# RCShield-avr-v4.net
KiCad netlist of a schematic drawn in EAGLE
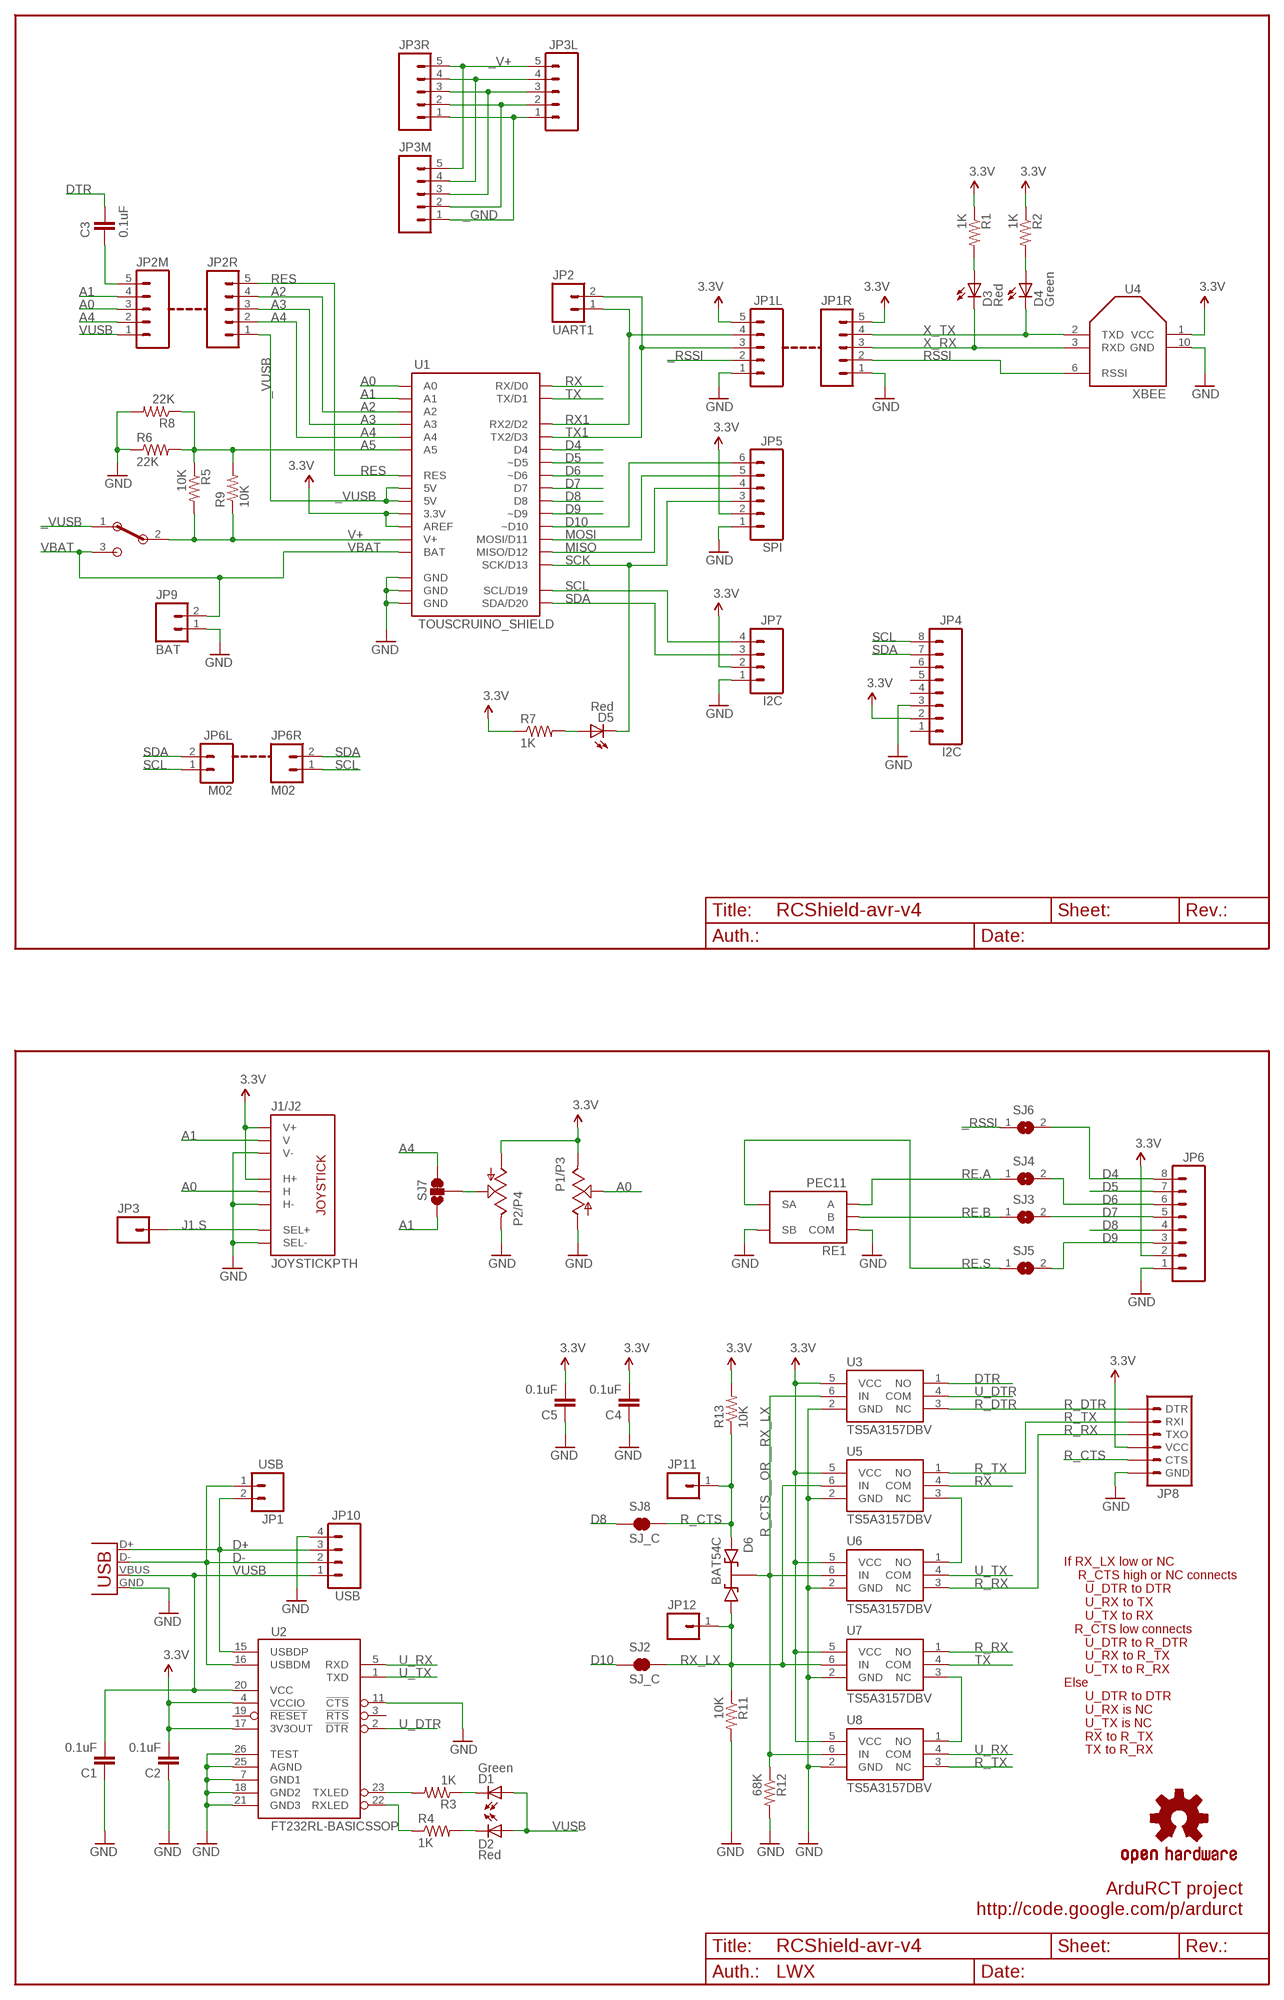
[diagram p0: schematic, sheet 1]

(export (version "E")
  (design (tool "Eeschema 10.0.6"))
  (components
    (comp (ref "C1")
      (value "0.1uF")
      (footprint "eagle-import:0805")
      (libsource (lib "eagle-import") (part "CAP0805"))
    )
    (comp (ref "C2")
      (value "0.1uF")
      (footprint "eagle-import:0805")
      (libsource (lib "eagle-import") (part "CAP0805"))
    )
    (comp (ref "C3")
      (value "0.1uF")
      (footprint "eagle-import:0805")
      (libsource (lib "eagle-import") (part "CAP0805"))
    )
    (comp (ref "C4")
      (value "0.1uF")
      (footprint "eagle-import:0805")
      (libsource (lib "eagle-import") (part "CAP0805"))
    )
    (comp (ref "C5")
      (value "0.1uF")
      (footprint "eagle-import:0805")
      (libsource (lib "eagle-import") (part "CAP0805"))
    )
    (comp (ref "D1")
      (value "Green")
      (footprint "eagle-import:LED")
      (libsource (lib "eagle-import") (part "LED"))
    )
    (comp (ref "D2")
      (value "Red")
      (footprint "eagle-import:LED")
      (libsource (lib "eagle-import") (part "LED"))
    )
    (comp (ref "D3")
      (value "Red")
      (footprint "eagle-import:LED")
      (libsource (lib "eagle-import") (part "LED"))
    )
    (comp (ref "D4")
      (value "Green")
      (footprint "eagle-import:LED")
      (libsource (lib "eagle-import") (part "LED"))
    )
    (comp (ref "D5")
      (value "Red")
      (footprint "eagle-import:LED")
      (libsource (lib "eagle-import") (part "LED"))
    )
    (comp (ref "D6")
      (value "BAT54C")
      (footprint "eagle-import:SOT23-3")
      (libsource (lib "eagle-import") (part "BAT54C"))
    )
    (comp (ref "J1/J2")
      (value "JOYSTICKPTH")
      (footprint "eagle-import:JOYSTICK")
      (libsource (lib "eagle-import") (part "JOYSTICKPTH"))
    )
    (comp (ref "JP1")
      (value "USB")
      (footprint "eagle-import:1X02")
      (libsource (lib "eagle-import") (part "M02"))
    )
    (comp (ref "JP1L")
      (value "M05")
      (footprint "eagle-import:2+3")
      (libsource (lib "eagle-import") (part "M05"))
    )
    (comp (ref "JP1R")
      (value "M05")
      (footprint "eagle-import:2+3")
      (libsource (lib "eagle-import") (part "M05"))
    )
    (comp (ref "JP2")
      (value "UART1")
      (footprint "eagle-import:1X02")
      (libsource (lib "eagle-import") (part "M02"))
    )
    (comp (ref "JP2M")
      (value "M05")
      (footprint "eagle-import:2+3")
      (libsource (lib "eagle-import") (part "M05"))
    )
    (comp (ref "JP2R")
      (value "M05")
      (footprint "eagle-import:2+3")
      (libsource (lib "eagle-import") (part "M05"))
    )
    (comp (ref "JP3")
      (value "M01PTH")
      (footprint "eagle-import:1X01")
      (libsource (lib "eagle-import") (part "M01PTH"))
    )
    (comp (ref "JP3L")
      (value "M05")
      (footprint "eagle-import:2+3")
      (libsource (lib "eagle-import") (part "M05"))
    )
    (comp (ref "JP3M")
      (value "M05")
      (footprint "eagle-import:2+3")
      (libsource (lib "eagle-import") (part "M05"))
    )
    (comp (ref "JP3R")
      (value "M05")
      (footprint "eagle-import:2+3")
      (libsource (lib "eagle-import") (part "M05"))
    )
    (comp (ref "JP4")
      (value "I2C")
      (footprint "eagle-import:1X08")
      (libsource (lib "eagle-import") (part "M08"))
    )
    (comp (ref "JP5")
      (value "SPI")
      (footprint "eagle-import:1X06")
      (libsource (lib "eagle-import") (part "M06SIP"))
    )
    (comp (ref "JP6")
      (value "M08")
      (footprint "eagle-import:1X08")
      (libsource (lib "eagle-import") (part "M08"))
    )
    (comp (ref "JP6L")
      (value "M02")
      (footprint "eagle-import:1X02")
      (libsource (lib "eagle-import") (part "M02"))
    )
    (comp (ref "JP6R")
      (value "M02")
      (footprint "eagle-import:1X02")
      (libsource (lib "eagle-import") (part "M02"))
    )
    (comp (ref "JP7")
      (value "I2C")
      (footprint "eagle-import:1X04")
      (libsource (lib "eagle-import") (part "M04"))
    )
    (comp (ref "JP8")
      (value "ARDUINO_SERIAL_PROGRAM")
      (footprint "eagle-import:1X06_F")
      (libsource (lib "eagle-import") (part "ARDUINO_SERIAL_PROGRAM"))
    )
    (comp (ref "JP9")
      (value "BAT")
      (footprint "eagle-import:1X02")
      (libsource (lib "eagle-import") (part "M02"))
    )
    (comp (ref "JP10")
      (value "USB")
      (footprint "eagle-import:1X04")
      (libsource (lib "eagle-import") (part "M04"))
    )
    (comp (ref "JP11")
      (value "M01SMALL")
      (footprint "eagle-import:1X01_S")
      (libsource (lib "eagle-import") (part "M01SMALL"))
    )
    (comp (ref "JP12")
      (value "M01SMALL")
      (footprint "eagle-import:1X01_S")
      (libsource (lib "eagle-import") (part "M01SMALL"))
    )
    (comp (ref "P1/P3")
      (value "POT")
      (footprint "eagle-import:ALPS_POT")
      (libsource (lib "eagle-import") (part "POT"))
    )
    (comp (ref "P2/P4")
      (value "POT")
      (footprint "eagle-import:ALPS_POT")
      (libsource (lib "eagle-import") (part "POT"))
    )
    (comp (ref "R1")
      (value "1K")
      (footprint "eagle-import:0805")
      (libsource (lib "eagle-import") (part "RESISTOR0805-RES"))
    )
    (comp (ref "R2")
      (value "1K")
      (footprint "eagle-import:0805")
      (libsource (lib "eagle-import") (part "RESISTOR0805-RES"))
    )
    (comp (ref "R3")
      (value "1K")
      (footprint "eagle-import:0805")
      (libsource (lib "eagle-import") (part "RESISTOR0805-RES"))
    )
    (comp (ref "R4")
      (value "1K")
      (footprint "eagle-import:0805")
      (libsource (lib "eagle-import") (part "RESISTOR0805-RES"))
    )
    (comp (ref "R5")
      (value "10K")
      (footprint "eagle-import:0805")
      (libsource (lib "eagle-import") (part "RESISTOR0805-RES"))
    )
    (comp (ref "R6")
      (value "22K")
      (footprint "eagle-import:0805")
      (libsource (lib "eagle-import") (part "RESISTOR0805-RES"))
    )
    (comp (ref "R7")
      (value "1K")
      (footprint "eagle-import:0805")
      (libsource (lib "eagle-import") (part "RESISTOR0805-RES"))
    )
    (comp (ref "R8")
      (value "22K")
      (footprint "eagle-import:0207_7")
      (libsource (lib "eagle-import") (part "R-US_0207/7"))
    )
    (comp (ref "R9")
      (value "10K")
      (footprint "eagle-import:0207_7")
      (libsource (lib "eagle-import") (part "R-US_0207/7"))
    )
    (comp (ref "R11")
      (value "10K")
      (footprint "eagle-import:0805")
      (libsource (lib "eagle-import") (part "RESISTOR0805-RES"))
    )
    (comp (ref "R12")
      (value "68K")
      (footprint "eagle-import:0805")
      (libsource (lib "eagle-import") (part "RESISTOR0805-RES"))
    )
    (comp (ref "R13")
      (value "10K")
      (footprint "eagle-import:0805")
      (libsource (lib "eagle-import") (part "RESISTOR0805-RES"))
    )
    (comp (ref "RE1")
      (value "PEC11")
      (footprint "eagle-import:PEC11")
      (libsource (lib "eagle-import") (part "PEC11"))
    )
    (comp (ref "S4")
      (value "EG1224")
      (footprint "eagle-import:EG1224")
      (libsource (lib "eagle-import") (part "EG1224"))
    )
    (comp (ref "SJ2")
      (value "SJ_C")
      (footprint "eagle-import:SJ_C")
      (libsource (lib "eagle-import") (part "SJ_C"))
    )
    (comp (ref "SJ3") (value "SJ") (footprint "eagle-import:SJ") (libsource (lib "eagle-import") (part "SJ")))
    (comp (ref "SJ4") (value "SJ") (footprint "eagle-import:SJ") (libsource (lib "eagle-import") (part "SJ")))
    (comp (ref "SJ5") (value "SJ") (footprint "eagle-import:SJ") (libsource (lib "eagle-import") (part "SJ")))
    (comp (ref "SJ6") (value "SJ") (footprint "eagle-import:SJ") (libsource (lib "eagle-import") (part "SJ")))
    (comp (ref "SJ7")
      (value "SJ_2WAYS_1-2W")
      (footprint "eagle-import:SJ_2WAYS_1-2")
      (libsource (lib "eagle-import") (part "SJ_2WAYS_1-2W"))
    )
    (comp (ref "SJ8")
      (value "SJ_C")
      (footprint "eagle-import:SJ_C")
      (libsource (lib "eagle-import") (part "SJ_C"))
    )
    (comp (ref "U$1")
      (value "OSHW-LOGOM")
      (footprint "eagle-import:OSHW-LOGO-M")
      (libsource (lib "eagle-import") (part "OSHW-LOGOM"))
    )
    (comp (ref "U1")
      (value "TOUSCRUINO_SHIELD")
      (footprint "eagle-import:TOUSCRUINO_SHIELD_SPLIT")
      (libsource (lib "eagle-import") (part "TOUSCRUINO_SHIELDSPLIT"))
    )
    (comp (ref "U2")
      (value "FT232RL-BASICSSOP")
      (footprint "eagle-import:SSOP28DB")
      (libsource (lib "eagle-import") (part "FT232RL-BASICSSOP"))
    )
    (comp (ref "U3")
      (value "TS5A3157DBV")
      (footprint "eagle-import:SOT23-6")
      (libsource (lib "eagle-import") (part "TS5A3157DBV"))
    )
    (comp (ref "U4")
      (value "XBEE")
      (footprint "eagle-import:XBEE-SMD")
      (libsource (lib "eagle-import") (part "XBEE-RSSI"))
    )
    (comp (ref "U5")
      (value "TS5A3157DBV")
      (footprint "eagle-import:SOT23-6")
      (libsource (lib "eagle-import") (part "TS5A3157DBV"))
    )
    (comp (ref "U6")
      (value "TS5A3157DBV")
      (footprint "eagle-import:SOT23-6")
      (libsource (lib "eagle-import") (part "TS5A3157DBV"))
    )
    (comp (ref "U7")
      (value "TS5A3157DBV")
      (footprint "eagle-import:SOT23-6")
      (libsource (lib "eagle-import") (part "TS5A3157DBV"))
    )
    (comp (ref "U8")
      (value "TS5A3157DBV")
      (footprint "eagle-import:SOT23-6")
      (libsource (lib "eagle-import") (part "TS5A3157DBV"))
    )
    (comp (ref "X1")
      (value "USB")
      (footprint "eagle-import:USB-MICROB")
      (libsource (lib "eagle-import") (part "USB"))
    )
  )
  (nets
    (net (code "1") (name "/A0") (class "Default")
      (node (ref "J1/J2") (pin "H2") (pinfunction "H_H2") (pintype "bidirectional"))
      (node (ref "JP2M") (pin "3") (pinfunction "3_3") (pintype "passive"))
      (node (ref "P1/P3") (pin "P$2") (pinfunction "S_P$2") (pintype "passive"))
      (node (ref "U1") (pin "A0") (pinfunction "A0_A0") (pintype "bidirectional"))
    )
    (net (code "2") (name "/A1") (class "Default")
      (node (ref "J1/J2") (pin "V2") (pinfunction "V_V2") (pintype "bidirectional"))
      (node (ref "JP2M") (pin "4") (pinfunction "4_4") (pintype "passive"))
      (node (ref "SJ7") (pin "3") (pinfunction "3_3") (pintype "passive"))
      (node (ref "U1") (pin "A1") (pinfunction "A1_A1") (pintype "bidirectional"))
    )
    (net (code "3") (name "/A2") (class "Default")
      (node (ref "JP2R") (pin "4") (pinfunction "4_4") (pintype "passive"))
      (node (ref "U1") (pin "A2") (pinfunction "A2_A2") (pintype "bidirectional"))
    )
    (net (code "4") (name "/A3") (class "Default")
      (node (ref "JP2R") (pin "3") (pinfunction "3_3") (pintype "passive"))
      (node (ref "U1") (pin "A3") (pinfunction "A3_A3") (pintype "bidirectional"))
    )
    (net (code "5") (name "/A4") (class "Default")
      (node (ref "JP2M") (pin "2") (pinfunction "2_2") (pintype "passive"))
      (node (ref "JP2R") (pin "2") (pinfunction "2_2") (pintype "passive"))
      (node (ref "SJ7") (pin "1") (pinfunction "1_1") (pintype "passive"))
      (node (ref "U1") (pin "A4") (pinfunction "A4_A4") (pintype "bidirectional"))
    )
    (net (code "6") (name "/A5") (class "Default")
      (node (ref "R5") (pin "1") (pinfunction "1_1") (pintype "passive"))
      (node (ref "R6") (pin "2") (pinfunction "2_2") (pintype "passive"))
      (node (ref "R8") (pin "1") (pinfunction "1_1") (pintype "passive"))
      (node (ref "R9") (pin "2") (pinfunction "2_2") (pintype "passive"))
      (node (ref "U1") (pin "A5") (pinfunction "A5_A5") (pintype "bidirectional"))
    )
    (net (code "7") (name "/D+") (class "Default")
      (node (ref "JP1") (pin "2") (pinfunction "2_2") (pintype "passive"))
      (node (ref "JP10") (pin "3") (pinfunction "3_3") (pintype "passive"))
      (node (ref "U2") (pin "15") (pinfunction "USBDP_15") (pintype "bidirectional"))
      (node (ref "X1") (pin "D+") (pinfunction "D+_D+") (pintype "bidirectional"))
    )
    (net (code "8") (name "/D-") (class "Default")
      (node (ref "JP1") (pin "1") (pinfunction "1_1") (pintype "passive"))
      (node (ref "JP10") (pin "2") (pinfunction "2_2") (pintype "passive"))
      (node (ref "U2") (pin "16") (pinfunction "USBDM_16") (pintype "bidirectional"))
      (node (ref "X1") (pin "D-") (pinfunction "D-_D-") (pintype "bidirectional"))
    )
    (net (code "9") (name "/D4") (class "Default")
      (node (ref "JP6") (pin "8") (pinfunction "8_8") (pintype "passive"))
      (node (ref "SJ6") (pin "2") (pinfunction "2_2") (pintype "passive"))
      (node (ref "U1") (pin "D4") (pinfunction "D4_D4") (pintype "bidirectional"))
    )
    (net (code "10") (name "/D5") (class "Default")
      (node (ref "JP6") (pin "7") (pinfunction "7_7") (pintype "passive"))
      (node (ref "U1") (pin "D5") (pinfunction "~{D5}_D5") (pintype "bidirectional"))
    )
    (net (code "11") (name "/D6") (class "Default")
      (node (ref "JP6") (pin "6") (pinfunction "6_6") (pintype "passive"))
      (node (ref "SJ4") (pin "2") (pinfunction "2_2") (pintype "passive"))
      (node (ref "U1") (pin "D6") (pinfunction "~{D6}_D6") (pintype "bidirectional"))
    )
    (net (code "12") (name "/D7") (class "Default")
      (node (ref "JP6") (pin "5") (pinfunction "5_5") (pintype "passive"))
      (node (ref "SJ3") (pin "2") (pinfunction "2_2") (pintype "passive"))
      (node (ref "U1") (pin "D7") (pinfunction "D7_D7") (pintype "bidirectional"))
    )
    (net (code "13") (name "/D8") (class "Default")
      (node (ref "JP6") (pin "4") (pinfunction "4_4") (pintype "passive"))
      (node (ref "SJ8") (pin "1") (pinfunction "1_1") (pintype "passive"))
      (node (ref "U1") (pin "D8") (pinfunction "D8_D8") (pintype "bidirectional"))
    )
    (net (code "14") (name "/D9") (class "Default")
      (node (ref "JP6") (pin "3") (pinfunction "3_3") (pintype "passive"))
      (node (ref "SJ5") (pin "2") (pinfunction "2_2") (pintype "passive"))
      (node (ref "U1") (pin "D9") (pinfunction "~{D9}_D9") (pintype "bidirectional"))
    )
    (net (code "15") (name "/D10") (class "Default")
      (node (ref "JP5") (pin "6") (pinfunction "6_6") (pintype "passive"))
      (node (ref "SJ2") (pin "1") (pinfunction "1_1") (pintype "passive"))
      (node (ref "U1") (pin "D10") (pinfunction "~{D10}_D10") (pintype "bidirectional"))
    )
    (net (code "16") (name "/DTR") (class "Default")
      (node (ref "C3") (pin "1") (pinfunction "1_1") (pintype "passive"))
      (node (ref "U3") (pin "1") (pinfunction "NO_1") (pintype "bidirectional"))
    )
    (net (code "17") (name "/J1.S") (class "Default")
      (node (ref "J1/J2") (pin "B1A") (pinfunction "SEL+_B1A") (pintype "bidirectional"))
      (node (ref "JP3") (pin "1") (pinfunction "1_1") (pintype "passive"))
    )
    (net (code "18") (name "/MISO") (class "Default")
      (node (ref "JP5") (pin "4") (pinfunction "4_4") (pintype "passive"))
      (node (ref "U1") (pin "D12") (pinfunction "MISO/D12_D12") (pintype "bidirectional"))
    )
    (net (code "19") (name "/MOSI") (class "Default")
      (node (ref "JP5") (pin "5") (pinfunction "5_5") (pintype "passive"))
      (node (ref "U1") (pin "D11") (pinfunction "MOSI/D11_D11") (pintype "bidirectional"))
    )
    (net (code "20") (name "/RE.A") (class "Default")
      (node (ref "RE1") (pin "A") (pinfunction "A_A") (pintype "bidirectional"))
      (node (ref "SJ4") (pin "1") (pinfunction "1_1") (pintype "passive"))
    )
    (net (code "21") (name "/RE.B") (class "Default")
      (node (ref "RE1") (pin "B") (pinfunction "B_B") (pintype "bidirectional"))
      (node (ref "SJ3") (pin "1") (pinfunction "1_1") (pintype "passive"))
    )
    (net (code "22") (name "/RE.S") (class "Default")
      (node (ref "RE1") (pin "S1") (pinfunction "SA_S1") (pintype "bidirectional"))
      (node (ref "SJ5") (pin "1") (pinfunction "1_1") (pintype "passive"))
    )
    (net (code "23") (name "/RES") (class "Default")
      (node (ref "JP2R") (pin "5") (pinfunction "5_5") (pintype "passive"))
      (node (ref "U1") (pin "RES") (pinfunction "RES_RES") (pintype "bidirectional"))
    )
    (net (code "24") (name "/RSSI") (class "Default")
      (node (ref "JP1R") (pin "2") (pinfunction "2_2") (pintype "passive"))
      (node (ref "U4") (pin "6") (pinfunction "RSSI_6") (pintype "bidirectional"))
    )
    (net (code "25") (name "/RX") (class "Default")
      (node (ref "U1") (pin "RX") (pinfunction "RX/D0_RX") (pintype "bidirectional"))
      (node (ref "U5") (pin "4") (pinfunction "COM_4") (pintype "bidirectional"))
    )
    (net (code "26") (name "/RX1") (class "Default")
      (node (ref "JP1L") (pin "4") (pinfunction "4_4") (pintype "passive"))
      (node (ref "JP2") (pin "1") (pinfunction "1_1") (pintype "passive"))
      (node (ref "U1") (pin "D2") (pinfunction "RX2/D2_D2") (pintype "bidirectional"))
    )
    (net (code "27") (name "/RX_LX") (class "Default")
      (node (ref "D6") (pin "1") (pinfunction "A1_1") (pintype "bidirectional"))
      (node (ref "JP12") (pin "1") (pinfunction "1_1") (pintype "passive"))
      (node (ref "R11") (pin "1") (pinfunction "1_1") (pintype "passive"))
      (node (ref "SJ2") (pin "2") (pinfunction "2_2") (pintype "passive"))
      (node (ref "U5") (pin "6") (pinfunction "IN_6") (pintype "bidirectional"))
      (node (ref "U7") (pin "6") (pinfunction "IN_6") (pintype "bidirectional"))
    )
    (net (code "28") (name "/R_CTS") (class "Default")
      (node (ref "D6") (pin "2") (pinfunction "A2_2") (pintype "bidirectional"))
      (node (ref "JP11") (pin "1") (pinfunction "1_1") (pintype "passive"))
      (node (ref "JP8") (pin "5") (pinfunction "CTS_5") (pintype "passive"))
      (node (ref "R13") (pin "1") (pinfunction "1_1") (pintype "passive"))
      (node (ref "SJ8") (pin "2") (pinfunction "2_2") (pintype "passive"))
    )
    (net (code "29") (name "/R_CTS__OR__RX_LX") (class "Default")
      (node (ref "D6") (pin "3") (pinfunction "K_3") (pintype "bidirectional"))
      (node (ref "R12") (pin "1") (pinfunction "1_1") (pintype "passive"))
      (node (ref "U3") (pin "6") (pinfunction "IN_6") (pintype "bidirectional"))
      (node (ref "U6") (pin "6") (pinfunction "IN_6") (pintype "bidirectional"))
      (node (ref "U8") (pin "6") (pinfunction "IN_6") (pintype "bidirectional"))
    )
    (net (code "30") (name "/R_DTR") (class "Default")
      (node (ref "JP8") (pin "1") (pinfunction "DTR_1") (pintype "passive"))
      (node (ref "U3") (pin "3") (pinfunction "NC_3") (pintype "bidirectional"))
    )
    (net (code "31") (name "/R_RX") (class "Default")
      (node (ref "JP8") (pin "3") (pinfunction "TXO_3") (pintype "passive"))
      (node (ref "U6") (pin "3") (pinfunction "NC_3") (pintype "bidirectional"))
      (node (ref "U7") (pin "1") (pinfunction "NO_1") (pintype "bidirectional"))
    )
    (net (code "32") (name "/R_TX") (class "Default")
      (node (ref "JP8") (pin "2") (pinfunction "RXI_2") (pintype "passive"))
      (node (ref "U5") (pin "1") (pinfunction "NO_1") (pintype "bidirectional"))
      (node (ref "U8") (pin "3") (pinfunction "NC_3") (pintype "bidirectional"))
    )
    (net (code "33") (name "/SCK") (class "Default")
      (node (ref "D5") (pin "C1") (pinfunction "C_C1") (pintype "passive"))
      (node (ref "JP5") (pin "3") (pinfunction "3_3") (pintype "passive"))
      (node (ref "U1") (pin "D13") (pinfunction "SCK/D13_D13") (pintype "bidirectional"))
    )
    (net (code "34") (name "/SCL") (class "Default")
      (node (ref "JP4") (pin "8") (pinfunction "8_8") (pintype "passive"))
      (node (ref "JP6L") (pin "1") (pinfunction "1_1") (pintype "passive"))
      (node (ref "JP6R") (pin "1") (pinfunction "1_1") (pintype "passive"))
      (node (ref "JP7") (pin "4") (pinfunction "4_4") (pintype "passive"))
      (node (ref "U1") (pin "SCL") (pinfunction "SCL/D19_SCL") (pintype "bidirectional"))
    )
    (net (code "35") (name "/SDA") (class "Default")
      (node (ref "JP4") (pin "7") (pinfunction "7_7") (pintype "passive"))
      (node (ref "JP6L") (pin "2") (pinfunction "2_2") (pintype "passive"))
      (node (ref "JP6R") (pin "2") (pinfunction "2_2") (pintype "passive"))
      (node (ref "JP7") (pin "3") (pinfunction "3_3") (pintype "passive"))
      (node (ref "U1") (pin "SDA") (pinfunction "SDA/D20_SDA") (pintype "bidirectional"))
    )
    (net (code "36") (name "/TX") (class "Default")
      (node (ref "U1") (pin "TX") (pinfunction "TX/D1_TX") (pintype "bidirectional"))
      (node (ref "U7") (pin "4") (pinfunction "COM_4") (pintype "bidirectional"))
    )
    (net (code "37") (name "/TX1") (class "Default")
      (node (ref "JP1L") (pin "3") (pinfunction "3_3") (pintype "passive"))
      (node (ref "JP2") (pin "2") (pinfunction "2_2") (pintype "passive"))
      (node (ref "U1") (pin "D3") (pinfunction "TX2/D3_D3") (pintype "bidirectional"))
    )
    (net (code "38") (name "/U_DTR") (class "Default")
      (node (ref "U2") (pin "2") (pinfunction "~{DTR}_2") (pintype "bidirectional"))
      (node (ref "U3") (pin "4") (pinfunction "COM_4") (pintype "bidirectional"))
    )
    (net (code "39") (name "/U_RX") (class "Default")
      (node (ref "U2") (pin "5") (pinfunction "RXD_5") (pintype "input"))
      (node (ref "U8") (pin "4") (pinfunction "COM_4") (pintype "bidirectional"))
    )
    (net (code "40") (name "/U_TX") (class "Default")
      (node (ref "U2") (pin "1") (pinfunction "TXD_1") (pintype "output"))
      (node (ref "U6") (pin "4") (pinfunction "COM_4") (pintype "bidirectional"))
    )
    (net (code "41") (name "/V+") (class "Default")
      (node (ref "R5") (pin "2") (pinfunction "2_2") (pintype "passive"))
      (node (ref "R9") (pin "1") (pinfunction "1_1") (pintype "passive"))
      (node (ref "S4") (pin "2") (pinfunction "2_2") (pintype "bidirectional"))
      (node (ref "U1") (pin "V+") (pinfunction "V+_V+") (pintype "bidirectional"))
    )
    (net (code "42") (name "/VBAT") (class "Default")
      (node (ref "JP9") (pin "2") (pinfunction "2_2") (pintype "passive"))
      (node (ref "S4") (pin "3") (pinfunction "3_3") (pintype "bidirectional"))
      (node (ref "U1") (pin "BAT") (pinfunction "BAT_BAT") (pintype "bidirectional"))
    )
    (net (code "43") (name "/VUSB") (class "Default")
      (node (ref "C1") (pin "2") (pinfunction "2_2") (pintype "passive"))
      (node (ref "D1") (pin "A1") (pinfunction "A_A1") (pintype "passive"))
      (node (ref "D2") (pin "A1") (pinfunction "A_A1") (pintype "passive"))
      (node (ref "JP10") (pin "1") (pinfunction "1_1") (pintype "passive"))
      (node (ref "JP2M") (pin "1") (pinfunction "1_1") (pintype "passive"))
      (node (ref "U2") (pin "20") (pinfunction "VCC_20") (pintype "bidirectional"))
      (node (ref "X1") (pin "VBUS") (pinfunction "VBUS_VBUS") (pintype "bidirectional"))
    )
    (net (code "44") (name "/X_RX") (class "Default")
      (node (ref "D3") (pin "C1") (pinfunction "C_C1") (pintype "passive"))
      (node (ref "JP1R") (pin "3") (pinfunction "3_3") (pintype "passive"))
      (node (ref "U4") (pin "3") (pinfunction "RXD_3") (pintype "bidirectional"))
    )
    (net (code "45") (name "/X_TX") (class "Default")
      (node (ref "D4") (pin "C1") (pinfunction "C_C1") (pintype "passive"))
      (node (ref "JP1R") (pin "4") (pinfunction "4_4") (pintype "passive"))
      (node (ref "U4") (pin "2") (pinfunction "TXD_2") (pintype "bidirectional"))
    )
    (net (code "46") (name "/_GND") (class "Default")
      (node (ref "JP3L") (pin "1") (pinfunction "1_1") (pintype "passive"))
      (node (ref "JP3M") (pin "1") (pinfunction "1_1") (pintype "passive"))
      (node (ref "JP3R") (pin "1") (pinfunction "1_1") (pintype "passive"))
    )
    (net (code "47") (name "/_RSSI") (class "Default")
      (node (ref "JP1L") (pin "2") (pinfunction "2_2") (pintype "passive"))
      (node (ref "SJ6") (pin "1") (pinfunction "1_1") (pintype "passive"))
    )
    (net (code "48") (name "/_V+") (class "Default")
      (node (ref "JP3L") (pin "5") (pinfunction "5_5") (pintype "passive"))
      (node (ref "JP3M") (pin "5") (pinfunction "5_5") (pintype "passive"))
      (node (ref "JP3R") (pin "5") (pinfunction "5_5") (pintype "passive"))
    )
    (net (code "49") (name "/_VUSB") (class "Default")
      (node (ref "JP2R") (pin "1") (pinfunction "1_1") (pintype "passive"))
      (node (ref "S4") (pin "1") (pinfunction "1_1") (pintype "bidirectional"))
      (node (ref "U1") (pin "5V@0") (pinfunction "5V_5V@0") (pintype "bidirectional"))
      (node (ref "U1") (pin "5V@1") (pinfunction "5V_5V@1") (pintype "bidirectional"))
    )
    (net (code "50") (name "3.3V") (class "Default")
      (node (ref "C2") (pin "2") (pinfunction "2_2") (pintype "passive"))
      (node (ref "C4") (pin "2") (pinfunction "2_2") (pintype "passive"))
      (node (ref "C5") (pin "2") (pinfunction "2_2") (pintype "passive"))
      (node (ref "J1/J2") (pin "H1") (pinfunction "H+_H1") (pintype "bidirectional"))
      (node (ref "J1/J2") (pin "V1") (pinfunction "V+_V1") (pintype "bidirectional"))
      (node (ref "JP1L") (pin "5") (pinfunction "5_5") (pintype "passive"))
      (node (ref "JP1R") (pin "5") (pinfunction "5_5") (pintype "passive"))
      (node (ref "JP4") (pin "2") (pinfunction "2_2") (pintype "passive"))
      (node (ref "JP5") (pin "2") (pinfunction "2_2") (pintype "passive"))
      (node (ref "JP6") (pin "2") (pinfunction "2_2") (pintype "passive"))
      (node (ref "JP7") (pin "2") (pinfunction "2_2") (pintype "passive"))
      (node (ref "JP8") (pin "4") (pinfunction "VCC_4") (pintype "passive"))
      (node (ref "P1/P3") (pin "P$1") (pinfunction "E_P$1") (pintype "passive"))
      (node (ref "P2/P4") (pin "P$3") (pinfunction "A_P$3") (pintype "passive"))
      (node (ref "R1") (pin "1") (pinfunction "1_1") (pintype "passive"))
      (node (ref "R13") (pin "2") (pinfunction "2_2") (pintype "passive"))
      (node (ref "R2") (pin "1") (pinfunction "1_1") (pintype "passive"))
      (node (ref "R7") (pin "1") (pinfunction "1_1") (pintype "passive"))
      (node (ref "U1") (pin "3.3V") (pinfunction "3.3V_3.3V") (pintype "bidirectional"))
      (node (ref "U1") (pin "AREF") (pinfunction "AREF_AREF") (pintype "bidirectional"))
      (node (ref "U2") (pin "17") (pinfunction "3V3OUT_17") (pintype "output"))
      (node (ref "U2") (pin "4") (pinfunction "VCCIO_4") (pintype "bidirectional"))
      (node (ref "U3") (pin "5") (pinfunction "VCC_5") (pintype "bidirectional"))
      (node (ref "U4") (pin "1") (pinfunction "VCC_1") (pintype "bidirectional"))
      (node (ref "U5") (pin "5") (pinfunction "VCC_5") (pintype "bidirectional"))
      (node (ref "U6") (pin "5") (pinfunction "VCC_5") (pintype "bidirectional"))
      (node (ref "U7") (pin "5") (pinfunction "VCC_5") (pintype "bidirectional"))
      (node (ref "U8") (pin "5") (pinfunction "VCC_5") (pintype "bidirectional"))
    )
    (net (code "51") (name "GND") (class "Default")
      (node (ref "C1") (pin "1") (pinfunction "1_1") (pintype "passive"))
      (node (ref "C2") (pin "1") (pinfunction "1_1") (pintype "passive"))
      (node (ref "C4") (pin "1") (pinfunction "1_1") (pintype "passive"))
      (node (ref "C5") (pin "1") (pinfunction "1_1") (pintype "passive"))
      (node (ref "J1/J2") (pin "B2A") (pinfunction "SEL-_B2A") (pintype "bidirectional"))
      (node (ref "J1/J2") (pin "H3") (pinfunction "H-_H3") (pintype "bidirectional"))
      (node (ref "J1/J2") (pin "V3") (pinfunction "V-_V3") (pintype "bidirectional"))
      (node (ref "JP10") (pin "4") (pinfunction "4_4") (pintype "passive"))
      (node (ref "JP1L") (pin "1") (pinfunction "1_1") (pintype "passive"))
      (node (ref "JP1R") (pin "1") (pinfunction "1_1") (pintype "passive"))
      (node (ref "JP4") (pin "3") (pinfunction "3_3") (pintype "passive"))
      (node (ref "JP5") (pin "1") (pinfunction "1_1") (pintype "passive"))
      (node (ref "JP6") (pin "1") (pinfunction "1_1") (pintype "passive"))
      (node (ref "JP7") (pin "1") (pinfunction "1_1") (pintype "passive"))
      (node (ref "JP8") (pin "6") (pinfunction "GND_6") (pintype "passive"))
      (node (ref "JP9") (pin "1") (pinfunction "1_1") (pintype "passive"))
      (node (ref "P1/P3") (pin "P$3") (pinfunction "A_P$3") (pintype "passive"))
      (node (ref "P2/P4") (pin "P$1") (pinfunction "E_P$1") (pintype "passive"))
      (node (ref "R11") (pin "2") (pinfunction "2_2") (pintype "passive"))
      (node (ref "R12") (pin "2") (pinfunction "2_2") (pintype "passive"))
      (node (ref "R6") (pin "1") (pinfunction "1_1") (pintype "passive"))
      (node (ref "R8") (pin "2") (pinfunction "2_2") (pintype "passive"))
      (node (ref "RE1") (pin "C") (pinfunction "COM_C") (pintype "bidirectional"))
      (node (ref "RE1") (pin "S2") (pinfunction "SB_S2") (pintype "bidirectional"))
      (node (ref "U1") (pin "GND@0") (pinfunction "GND_GND@0") (pintype "bidirectional"))
      (node (ref "U1") (pin "GND@1") (pinfunction "GND_GND@1") (pintype "bidirectional"))
      (node (ref "U1") (pin "GND@2") (pinfunction "GND_GND@2") (pintype "bidirectional"))
      (node (ref "U2") (pin "11") (pinfunction "~{CTS}_11") (pintype "bidirectional"))
      (node (ref "U2") (pin "18") (pinfunction "GND2_18") (pintype "bidirectional"))
      (node (ref "U2") (pin "21") (pinfunction "GND3_21") (pintype "bidirectional"))
      (node (ref "U2") (pin "25") (pinfunction "AGND_25") (pintype "bidirectional"))
      (node (ref "U2") (pin "26") (pinfunction "TEST_26") (pintype "input"))
      (node (ref "U2") (pin "7") (pinfunction "GND1_7") (pintype "bidirectional"))
      (node (ref "U3") (pin "2") (pinfunction "GND_2") (pintype "bidirectional"))
      (node (ref "U4") (pin "10") (pinfunction "GND_10") (pintype "bidirectional"))
      (node (ref "U5") (pin "2") (pinfunction "GND_2") (pintype "bidirectional"))
      (node (ref "U6") (pin "2") (pinfunction "GND_2") (pintype "bidirectional"))
      (node (ref "U7") (pin "2") (pinfunction "GND_2") (pintype "bidirectional"))
      (node (ref "U8") (pin "2") (pinfunction "GND_2") (pintype "bidirectional"))
      (node (ref "X1") (pin "GND") (pinfunction "GND_GND") (pintype "bidirectional"))
    )
    (net (code "52") (name "Net-(C3-Pad2)") (class "Default")
      (node (ref "C3") (pin "2") (pinfunction "2_2") (pintype "passive"))
      (node (ref "JP2M") (pin "5") (pinfunction "5_5") (pintype "passive"))
    )
    (net (code "53") (name "Net-(D1-C)") (class "Default")
      (node (ref "D1") (pin "C1") (pinfunction "C_C1") (pintype "passive"))
      (node (ref "R3") (pin "1") (pinfunction "1_1") (pintype "passive"))
    )
    (net (code "54") (name "Net-(D2-C)") (class "Default")
      (node (ref "D2") (pin "C1") (pinfunction "C_C1") (pintype "passive"))
      (node (ref "R4") (pin "2") (pinfunction "2_2") (pintype "passive"))
    )
    (net (code "55") (name "Net-(D3-A)") (class "Default")
      (node (ref "D3") (pin "A1") (pinfunction "A_A1") (pintype "passive"))
      (node (ref "R1") (pin "2") (pinfunction "2_2") (pintype "passive"))
    )
    (net (code "56") (name "Net-(D4-A)") (class "Default")
      (node (ref "D4") (pin "A1") (pinfunction "A_A1") (pintype "passive"))
      (node (ref "R2") (pin "2") (pinfunction "2_2") (pintype "passive"))
    )
    (net (code "57") (name "Net-(D5-A)") (class "Default")
      (node (ref "D5") (pin "A1") (pinfunction "A_A1") (pintype "passive"))
      (node (ref "R7") (pin "2") (pinfunction "2_2") (pintype "passive"))
    )
    (net (code "58") (name "Net-(JP3L-Pad2)") (class "Default")
      (node (ref "JP3L") (pin "2") (pinfunction "2_2") (pintype "passive"))
      (node (ref "JP3M") (pin "2") (pinfunction "2_2") (pintype "passive"))
      (node (ref "JP3R") (pin "2") (pinfunction "2_2") (pintype "passive"))
    )
    (net (code "59") (name "Net-(JP3L-Pad3)") (class "Default")
      (node (ref "JP3L") (pin "3") (pinfunction "3_3") (pintype "passive"))
      (node (ref "JP3M") (pin "3") (pinfunction "3_3") (pintype "passive"))
      (node (ref "JP3R") (pin "3") (pinfunction "3_3") (pintype "passive"))
    )
    (net (code "60") (name "Net-(JP3L-Pad4)") (class "Default")
      (node (ref "JP3L") (pin "4") (pinfunction "4_4") (pintype "passive"))
      (node (ref "JP3M") (pin "4") (pinfunction "4_4") (pintype "passive"))
      (node (ref "JP3R") (pin "4") (pinfunction "4_4") (pintype "passive"))
    )
    (net (code "61") (name "Net-(P2/P4-S)") (class "Default")
      (node (ref "P2/P4") (pin "P$2") (pinfunction "S_P$2") (pintype "passive"))
      (node (ref "SJ7") (pin "2") (pinfunction "2_2") (pintype "passive"))
    )
    (net (code "62") (name "Net-(U2-RXLED)") (class "Default")
      (node (ref "R4") (pin "1") (pinfunction "1_1") (pintype "passive"))
      (node (ref "U2") (pin "22") (pinfunction "RXLED_22") (pintype "bidirectional"))
    )
    (net (code "63") (name "Net-(U2-TXLED)") (class "Default")
      (node (ref "R3") (pin "2") (pinfunction "2_2") (pintype "passive"))
      (node (ref "U2") (pin "23") (pinfunction "TXLED_23") (pintype "bidirectional"))
    )
    (net (code "64") (name "Net-(U5-NC)") (class "Default")
      (node (ref "U5") (pin "3") (pinfunction "NC_3") (pintype "bidirectional"))
      (node (ref "U6") (pin "1") (pinfunction "NO_1") (pintype "bidirectional"))
    )
    (net (code "65") (name "Net-(U7-NC)") (class "Default")
      (node (ref "U7") (pin "3") (pinfunction "NC_3") (pintype "bidirectional"))
      (node (ref "U8") (pin "1") (pinfunction "NO_1") (pintype "bidirectional"))
    )
    (net (code "66") (name "unconnected-(JP4-Pad1)") (class "Default")
      (node (ref "JP4") (pin "1") (pinfunction "1_1") (pintype "passive"))
    )
    (net (code "67") (name "unconnected-(JP4-Pad4)") (class "Default")
      (node (ref "JP4") (pin "4") (pinfunction "4_4") (pintype "passive"))
    )
    (net (code "68") (name "unconnected-(JP4-Pad5)") (class "Default")
      (node (ref "JP4") (pin "5") (pinfunction "5_5") (pintype "passive"))
    )
    (net (code "69") (name "unconnected-(JP4-Pad6)") (class "Default")
      (node (ref "JP4") (pin "6") (pinfunction "6_6") (pintype "passive"))
    )
    (net (code "70") (name "unconnected-(U2-~{RESET}-Pad19)") (class "Default")
      (node (ref "U2") (pin "19") (pinfunction "~{RESET}_19") (pintype "bidirectional"))
    )
    (net (code "71") (name "unconnected-(U2-~{RTS}-Pad3)") (class "Default")
      (node (ref "U2") (pin "3") (pinfunction "~{RTS}_3") (pintype "bidirectional"))
    )
  )
)
